# pmod_vga6.net
KiCad netlist of a schematic drawn in EAGLE
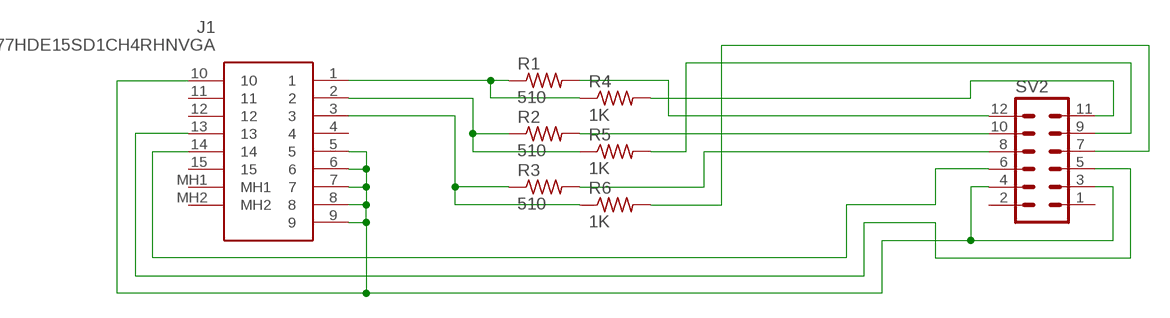
[diagram p0: schematic, sheet 1]

(export (version "E")
  (design (tool "Eeschema 10.0.6"))
  (components
    (comp (ref "J1")
      (value "L77HDE15SD1CH4RHNVGA")
      (footprint "eagle-import:L77HDE15SD1CH4RHNVGA")
      (fields (field (name "MOUSER_PART_NUMBER") "523-7HDE15SDH4RHNVGA"))
      (libsource (lib "eagle-import") (part "L77HDE15SD1CH4RHNVGA"))
    )
    (comp (ref "R1")
      (value "510")
      (footprint "eagle-import:R0805")
      (libsource (lib "eagle-import") (part "R-US_R0805"))
    )
    (comp (ref "R2")
      (value "510")
      (footprint "eagle-import:R0805")
      (libsource (lib "eagle-import") (part "R-US_R0805"))
    )
    (comp (ref "R3")
      (value "510")
      (footprint "eagle-import:R0805")
      (libsource (lib "eagle-import") (part "R-US_R0805"))
    )
    (comp (ref "R4")
      (value "1K")
      (footprint "eagle-import:R0805")
      (libsource (lib "eagle-import") (part "R-US_R0805"))
    )
    (comp (ref "R5")
      (value "1K")
      (footprint "eagle-import:R0805")
      (libsource (lib "eagle-import") (part "R-US_R0805"))
    )
    (comp (ref "R6")
      (value "1K")
      (footprint "eagle-import:R0805")
      (libsource (lib "eagle-import") (part "R-US_R0805"))
    )
    (comp (ref "SV2")
      (value "MA06-2")
      (footprint "eagle-import:MA06-2")
      (libsource (lib "eagle-import") (part "MA06-2"))
    )
  )
  (nets
    (net (code "1") (name "Net-(J1-Pad1)") (class "Default")
      (node (ref "J1") (pin "1") (pinfunction "1_1") (pintype "bidirectional"))
      (node (ref "R1") (pin "1") (pinfunction "1_1") (pintype "passive"))
      (node (ref "R4") (pin "1") (pinfunction "1_1") (pintype "passive"))
    )
    (net (code "2") (name "Net-(J1-Pad2)") (class "Default")
      (node (ref "J1") (pin "2") (pinfunction "2_2") (pintype "bidirectional"))
      (node (ref "R2") (pin "1") (pinfunction "1_1") (pintype "passive"))
      (node (ref "R5") (pin "1") (pinfunction "1_1") (pintype "passive"))
    )
    (net (code "3") (name "Net-(J1-Pad3)") (class "Default")
      (node (ref "J1") (pin "3") (pinfunction "3_3") (pintype "bidirectional"))
      (node (ref "R3") (pin "1") (pinfunction "1_1") (pintype "passive"))
      (node (ref "R6") (pin "1") (pinfunction "1_1") (pintype "passive"))
    )
    (net (code "4") (name "Net-(J1-Pad10)") (class "Default")
      (node (ref "J1") (pin "10") (pinfunction "10_10") (pintype "bidirectional"))
      (node (ref "J1") (pin "5") (pinfunction "5_5") (pintype "bidirectional"))
      (node (ref "J1") (pin "6") (pinfunction "6_6") (pintype "bidirectional"))
      (node (ref "J1") (pin "7") (pinfunction "7_7") (pintype "bidirectional"))
      (node (ref "J1") (pin "8") (pinfunction "8_8") (pintype "bidirectional"))
      (node (ref "J1") (pin "9") (pinfunction "9_9") (pintype "bidirectional"))
      (node (ref "SV2") (pin "3") (pinfunction "3_3") (pintype "passive"))
      (node (ref "SV2") (pin "4") (pinfunction "4_4") (pintype "passive"))
    )
    (net (code "5") (name "Net-(J1-Pad13)") (class "Default")
      (node (ref "J1") (pin "13") (pinfunction "13_13") (pintype "bidirectional"))
      (node (ref "SV2") (pin "5") (pinfunction "5_5") (pintype "passive"))
    )
    (net (code "6") (name "Net-(J1-Pad14)") (class "Default")
      (node (ref "J1") (pin "14") (pinfunction "14_14") (pintype "bidirectional"))
      (node (ref "SV2") (pin "6") (pinfunction "6_6") (pintype "passive"))
    )
    (net (code "7") (name "Net-(R1-Pad2)") (class "Default")
      (node (ref "R1") (pin "2") (pinfunction "2_2") (pintype "passive"))
      (node (ref "SV2") (pin "12") (pinfunction "12_12") (pintype "passive"))
    )
    (net (code "8") (name "Net-(R2-Pad2)") (class "Default")
      (node (ref "R2") (pin "2") (pinfunction "2_2") (pintype "passive"))
      (node (ref "SV2") (pin "10") (pinfunction "10_10") (pintype "passive"))
    )
    (net (code "9") (name "Net-(R3-Pad2)") (class "Default")
      (node (ref "R3") (pin "2") (pinfunction "2_2") (pintype "passive"))
      (node (ref "SV2") (pin "8") (pinfunction "8_8") (pintype "passive"))
    )
    (net (code "10") (name "Net-(R4-Pad2)") (class "Default")
      (node (ref "R4") (pin "2") (pinfunction "2_2") (pintype "passive"))
      (node (ref "SV2") (pin "11") (pinfunction "11_11") (pintype "passive"))
    )
    (net (code "11") (name "Net-(R5-Pad2)") (class "Default")
      (node (ref "R5") (pin "2") (pinfunction "2_2") (pintype "passive"))
      (node (ref "SV2") (pin "9") (pinfunction "9_9") (pintype "passive"))
    )
    (net (code "12") (name "Net-(R6-Pad2)") (class "Default")
      (node (ref "R6") (pin "2") (pinfunction "2_2") (pintype "passive"))
      (node (ref "SV2") (pin "7") (pinfunction "7_7") (pintype "passive"))
    )
    (net (code "13") (name "unconnected-(J1-Pad4)") (class "Default")
      (node (ref "J1") (pin "4") (pinfunction "4_4") (pintype "bidirectional"))
    )
    (net (code "14") (name "unconnected-(J1-Pad11)") (class "Default")
      (node (ref "J1") (pin "11") (pinfunction "11_11") (pintype "bidirectional"))
    )
    (net (code "15") (name "unconnected-(J1-Pad12)") (class "Default")
      (node (ref "J1") (pin "12") (pinfunction "12_12") (pintype "bidirectional"))
    )
    (net (code "16") (name "unconnected-(J1-Pad15)") (class "Default")
      (node (ref "J1") (pin "15") (pinfunction "15_15") (pintype "bidirectional"))
    )
    (net (code "17") (name "unconnected-(J1-PadMH1)") (class "Default")
      (node (ref "J1") (pin "MH1") (pinfunction "MH1_MH1") (pintype "bidirectional"))
    )
    (net (code "18") (name "unconnected-(J1-PadMH2)") (class "Default")
      (node (ref "J1") (pin "MH2") (pinfunction "MH2_MH2") (pintype "bidirectional"))
    )
    (net (code "19") (name "unconnected-(SV2-Pad1)") (class "Default")
      (node (ref "SV2") (pin "1") (pinfunction "1_1") (pintype "passive"))
    )
    (net (code "20") (name "unconnected-(SV2-Pad2)") (class "Default")
      (node (ref "SV2") (pin "2") (pinfunction "2_2") (pintype "passive"))
    )
  )
)
